# Transistors.net
KiCad netlist of a schematic drawn in EAGLE
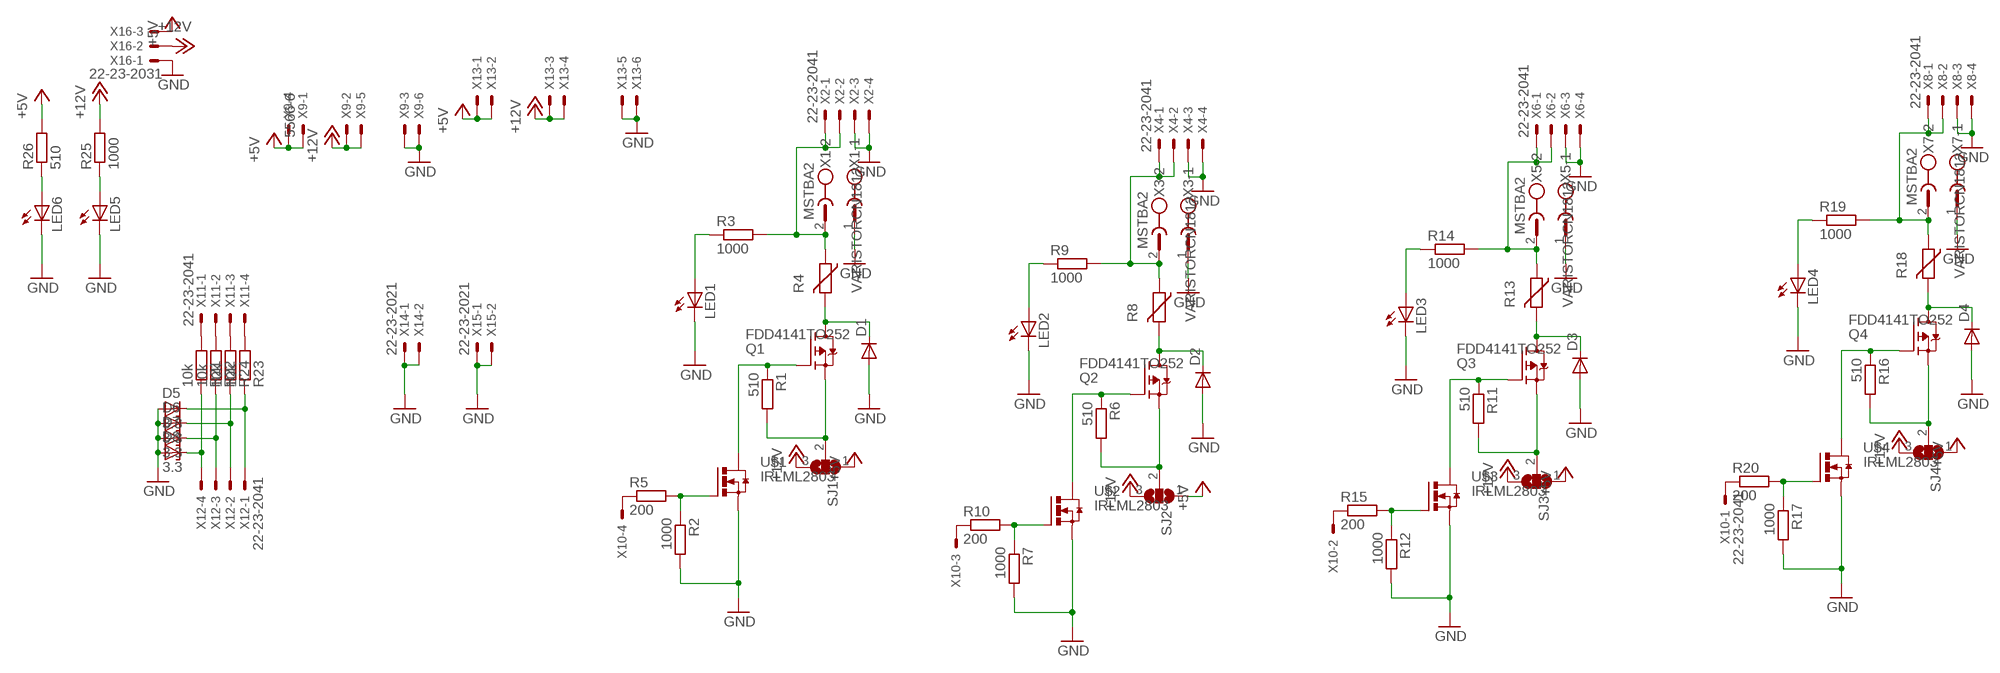
[diagram p0: schematic, sheet 1]

(export (version "E")
  (design (tool "Eeschema 10.0.6"))
  (components
    (comp (ref "D1")
      (value "DIODE-SMB")
      (footprint "eagle-import:SMB")
      (libsource (lib "eagle-import") (part "DIODE-SMB"))
    )
    (comp (ref "D2")
      (value "DIODE-SMB")
      (footprint "eagle-import:SMB")
      (libsource (lib "eagle-import") (part "DIODE-SMB"))
    )
    (comp (ref "D3")
      (value "DIODE-SMB")
      (footprint "eagle-import:SMB")
      (libsource (lib "eagle-import") (part "DIODE-SMB"))
    )
    (comp (ref "D4")
      (value "DIODE-SMB")
      (footprint "eagle-import:SMB")
      (libsource (lib "eagle-import") (part "DIODE-SMB"))
    )
    (comp (ref "D5")
      (value "3.3")
      (footprint "eagle-import:SOD80C")
      (libsource (lib "eagle-import") (part "ZENER-DIODESOD80C"))
    )
    (comp (ref "D6")
      (value "3.3")
      (footprint "eagle-import:SOD80C")
      (libsource (lib "eagle-import") (part "ZENER-DIODESOD80C"))
    )
    (comp (ref "D7")
      (value "3.3")
      (footprint "eagle-import:SOD80C")
      (libsource (lib "eagle-import") (part "ZENER-DIODESOD80C"))
    )
    (comp (ref "D8")
      (value "3.3")
      (footprint "eagle-import:SOD80C")
      (libsource (lib "eagle-import") (part "ZENER-DIODESOD80C"))
    )
    (comp (ref "LED1")
      (value "LEDCHIPLED_1206")
      (footprint "eagle-import:CHIPLED_1206")
      (libsource (lib "eagle-import") (part "LEDCHIPLED_1206"))
    )
    (comp (ref "LED2")
      (value "LEDCHIPLED_1206")
      (footprint "eagle-import:CHIPLED_1206")
      (libsource (lib "eagle-import") (part "LEDCHIPLED_1206"))
    )
    (comp (ref "LED3")
      (value "LEDCHIPLED_1206")
      (footprint "eagle-import:CHIPLED_1206")
      (libsource (lib "eagle-import") (part "LEDCHIPLED_1206"))
    )
    (comp (ref "LED4")
      (value "LEDCHIPLED_1206")
      (footprint "eagle-import:CHIPLED_1206")
      (libsource (lib "eagle-import") (part "LEDCHIPLED_1206"))
    )
    (comp (ref "LED5")
      (value "LEDCHIPLED_1206")
      (footprint "eagle-import:CHIPLED_1206")
      (libsource (lib "eagle-import") (part "LEDCHIPLED_1206"))
    )
    (comp (ref "LED6")
      (value "LEDCHIPLED_1206")
      (footprint "eagle-import:CHIPLED_1206")
      (libsource (lib "eagle-import") (part "LEDCHIPLED_1206"))
    )
    (comp (ref "Q1")
      (value "FDD4141TO252")
      (footprint "eagle-import:TO252")
      (libsource (lib "eagle-import") (part "FDD4141TO252"))
    )
    (comp (ref "Q2")
      (value "FDD4141TO252")
      (footprint "eagle-import:TO252")
      (libsource (lib "eagle-import") (part "FDD4141TO252"))
    )
    (comp (ref "Q3")
      (value "FDD4141TO252")
      (footprint "eagle-import:TO252")
      (libsource (lib "eagle-import") (part "FDD4141TO252"))
    )
    (comp (ref "Q4")
      (value "FDD4141TO252")
      (footprint "eagle-import:TO252")
      (libsource (lib "eagle-import") (part "FDD4141TO252"))
    )
    (comp (ref "R1")
      (value "510")
      (footprint "eagle-import:M0805")
      (libsource (lib "eagle-import") (part "R-EU_M0805"))
    )
    (comp (ref "R2")
      (value "1000")
      (footprint "eagle-import:M0805")
      (libsource (lib "eagle-import") (part "R-EU_M0805"))
    )
    (comp (ref "R3")
      (value "1000")
      (footprint "eagle-import:M0805")
      (libsource (lib "eagle-import") (part "R-EU_M0805"))
    )
    (comp (ref "R4")
      (value "VARISTORCN1812")
      (footprint "eagle-import:CT_CN1812")
      (libsource (lib "eagle-import") (part "VARISTORCN1812"))
    )
    (comp (ref "R5")
      (value "200")
      (footprint "eagle-import:M0805")
      (libsource (lib "eagle-import") (part "R-EU_M0805"))
    )
    (comp (ref "R6")
      (value "510")
      (footprint "eagle-import:M0805")
      (libsource (lib "eagle-import") (part "R-EU_M0805"))
    )
    (comp (ref "R7")
      (value "1000")
      (footprint "eagle-import:M0805")
      (libsource (lib "eagle-import") (part "R-EU_M0805"))
    )
    (comp (ref "R8")
      (value "VARISTORCN1812")
      (footprint "eagle-import:CT_CN1812")
      (libsource (lib "eagle-import") (part "VARISTORCN1812"))
    )
    (comp (ref "R9")
      (value "1000")
      (footprint "eagle-import:M0805")
      (libsource (lib "eagle-import") (part "R-EU_M0805"))
    )
    (comp (ref "R10")
      (value "200")
      (footprint "eagle-import:M0805")
      (libsource (lib "eagle-import") (part "R-EU_M0805"))
    )
    (comp (ref "R11")
      (value "510")
      (footprint "eagle-import:M0805")
      (libsource (lib "eagle-import") (part "R-EU_M0805"))
    )
    (comp (ref "R12")
      (value "1000")
      (footprint "eagle-import:M0805")
      (libsource (lib "eagle-import") (part "R-EU_M0805"))
    )
    (comp (ref "R13")
      (value "VARISTORCN1812")
      (footprint "eagle-import:CT_CN1812")
      (libsource (lib "eagle-import") (part "VARISTORCN1812"))
    )
    (comp (ref "R14")
      (value "1000")
      (footprint "eagle-import:M0805")
      (libsource (lib "eagle-import") (part "R-EU_M0805"))
    )
    (comp (ref "R15")
      (value "200")
      (footprint "eagle-import:M0805")
      (libsource (lib "eagle-import") (part "R-EU_M0805"))
    )
    (comp (ref "R16")
      (value "510")
      (footprint "eagle-import:M0805")
      (libsource (lib "eagle-import") (part "R-EU_M0805"))
    )
    (comp (ref "R17")
      (value "1000")
      (footprint "eagle-import:M0805")
      (libsource (lib "eagle-import") (part "R-EU_M0805"))
    )
    (comp (ref "R18")
      (value "VARISTORCN1812")
      (footprint "eagle-import:CT_CN1812")
      (libsource (lib "eagle-import") (part "VARISTORCN1812"))
    )
    (comp (ref "R19")
      (value "1000")
      (footprint "eagle-import:M0805")
      (libsource (lib "eagle-import") (part "R-EU_M0805"))
    )
    (comp (ref "R20")
      (value "200")
      (footprint "eagle-import:M0805")
      (libsource (lib "eagle-import") (part "R-EU_M0805"))
    )
    (comp (ref "R21")
      (value "10k")
      (footprint "eagle-import:M0805")
      (libsource (lib "eagle-import") (part "R-EU_M0805"))
    )
    (comp (ref "R22")
      (value "10k")
      (footprint "eagle-import:M0805")
      (libsource (lib "eagle-import") (part "R-EU_M0805"))
    )
    (comp (ref "R23")
      (value "10k")
      (footprint "eagle-import:M0805")
      (libsource (lib "eagle-import") (part "R-EU_M0805"))
    )
    (comp (ref "R24")
      (value "10k")
      (footprint "eagle-import:M0805")
      (libsource (lib "eagle-import") (part "R-EU_M0805"))
    )
    (comp (ref "R25")
      (value "1000")
      (footprint "eagle-import:M0805")
      (libsource (lib "eagle-import") (part "R-EU_M0805"))
    )
    (comp (ref "R26")
      (value "510")
      (footprint "eagle-import:M0805")
      (libsource (lib "eagle-import") (part "R-EU_M0805"))
    )
    (comp (ref "SJ1")
      (value "SJ2W")
      (footprint "eagle-import:SJ_2")
      (libsource (lib "eagle-import") (part "SJ2W"))
    )
    (comp (ref "SJ2")
      (value "SJ2W")
      (footprint "eagle-import:SJ_2")
      (libsource (lib "eagle-import") (part "SJ2W"))
    )
    (comp (ref "SJ3")
      (value "SJ2W")
      (footprint "eagle-import:SJ_2")
      (libsource (lib "eagle-import") (part "SJ2W"))
    )
    (comp (ref "SJ4")
      (value "SJ2W")
      (footprint "eagle-import:SJ_2")
      (libsource (lib "eagle-import") (part "SJ2W"))
    )
    (comp (ref "U$1")
      (value "IRLML2803")
      (footprint "eagle-import:SUPER-SOT3")
      (libsource (lib "eagle-import") (part "IRLML2803"))
    )
    (comp (ref "U$2")
      (value "IRLML2803")
      (footprint "eagle-import:SUPER-SOT3")
      (libsource (lib "eagle-import") (part "IRLML2803"))
    )
    (comp (ref "U$3")
      (value "IRLML2803")
      (footprint "eagle-import:SUPER-SOT3")
      (libsource (lib "eagle-import") (part "IRLML2803"))
    )
    (comp (ref "U$4")
      (value "IRLML2803")
      (footprint "eagle-import:SUPER-SOT3")
      (libsource (lib "eagle-import") (part "IRLML2803"))
    )
    (comp (ref "X1")
      (value "MSTBA2")
      (footprint "eagle-import:MSTBA2")
      (fields (field (name "MF") "FARNELL") (field (name "MPN") "1757242"))
      (libsource (lib "eagle-import") (part "MSTBA2"))
    )
    (comp (ref "X2")
      (value "22-23-2041")
      (footprint "eagle-import:22-23-2041")
      (fields (field (name "MF") "MOLEX"))
      (libsource (lib "eagle-import") (part "22-23-2041"))
    )
    (comp (ref "X3")
      (value "MSTBA2")
      (footprint "eagle-import:MSTBA2")
      (fields (field (name "MF") "FARNELL") (field (name "MPN") "1757242"))
      (libsource (lib "eagle-import") (part "MSTBA2"))
    )
    (comp (ref "X4")
      (value "22-23-2041")
      (footprint "eagle-import:22-23-2041")
      (fields (field (name "MF") "MOLEX"))
      (libsource (lib "eagle-import") (part "22-23-2041"))
    )
    (comp (ref "X5")
      (value "MSTBA2")
      (footprint "eagle-import:MSTBA2")
      (fields (field (name "MF") "FARNELL") (field (name "MPN") "1757242"))
      (libsource (lib "eagle-import") (part "MSTBA2"))
    )
    (comp (ref "X6")
      (value "22-23-2041")
      (footprint "eagle-import:22-23-2041")
      (fields (field (name "MF") "MOLEX"))
      (libsource (lib "eagle-import") (part "22-23-2041"))
    )
    (comp (ref "X7")
      (value "MSTBA2")
      (footprint "eagle-import:MSTBA2")
      (fields (field (name "MF") "FARNELL") (field (name "MPN") "1757242"))
      (libsource (lib "eagle-import") (part "MSTBA2"))
    )
    (comp (ref "X8")
      (value "22-23-2041")
      (footprint "eagle-import:22-23-2041")
      (fields (field (name "MF") "MOLEX"))
      (libsource (lib "eagle-import") (part "22-23-2041"))
    )
    (comp (ref "X9")
      (value "5566-6")
      (footprint "eagle-import:5566-6")
      (fields (field (name "MPN") "95566-61002"))
      (libsource (lib "eagle-import") (part "5566-6"))
    )
    (comp (ref "X10")
      (value "22-23-2041")
      (footprint "eagle-import:22-23-2041")
      (fields (field (name "MF") "MOLEX"))
      (libsource (lib "eagle-import") (part "22-23-2041"))
    )
    (comp (ref "X11")
      (value "22-23-2041")
      (footprint "eagle-import:22-23-2041")
      (fields
        (field (name "MF") "MOLEX")
        (field (name "MF_1") "MOLEX")
        (field (name "MPN") "22-23-2041")
        (field (name "OC_FARNELL") "1462920")
        (field (name "OC_NEWARK") "38C0355")
      )
      (libsource (lib "eagle-import") (part "22-23-2041"))
    )
    (comp (ref "X12")
      (value "22-23-2041")
      (footprint "eagle-import:22-23-2041")
      (fields
        (field (name "MF") "MOLEX")
        (field (name "MF_1") "MOLEX")
        (field (name "MPN") "22-23-2041")
        (field (name "OC_FARNELL") "1462920")
        (field (name "OC_NEWARK") "38C0355")
      )
      (libsource (lib "eagle-import") (part "22-23-2041"))
    )
    (comp (ref "X13")
      (value "22-23-2061")
      (footprint "eagle-import:22-23-2061")
      (fields (field (name "MF") "MOLEX"))
      (libsource (lib "eagle-import") (part "22-23-2061"))
    )
    (comp (ref "X14")
      (value "22-23-2021")
      (footprint "eagle-import:22-23-2021")
      (fields (field (name "MF") "MOLEX"))
      (libsource (lib "eagle-import") (part "22-23-2021"))
    )
    (comp (ref "X15")
      (value "22-23-2021")
      (footprint "eagle-import:22-23-2021")
      (fields (field (name "MF") "MOLEX"))
      (libsource (lib "eagle-import") (part "22-23-2021"))
    )
    (comp (ref "X16")
      (value "22-23-2031")
      (footprint "eagle-import:22-23-2031")
      (fields (field (name "MF") "MOLEX"))
      (libsource (lib "eagle-import") (part "22-23-2031"))
    )
  )
  (nets
    (net (code "1") (name "+5V") (class "Default")
      (node (ref "R26") (pin "2") (pinfunction "2_2") (pintype "passive"))
      (node (ref "SJ1") (pin "1") (pinfunction "1_1") (pintype "passive"))
      (node (ref "SJ2") (pin "1") (pinfunction "1_1") (pintype "passive"))
      (node (ref "SJ3") (pin "1") (pinfunction "1_1") (pintype "passive"))
      (node (ref "SJ4") (pin "1") (pinfunction "1_1") (pintype "passive"))
      (node (ref "X13") (pin "1") (pinfunction "S_1") (pintype "passive"))
      (node (ref "X13") (pin "2") (pinfunction "S_2") (pintype "passive"))
      (node (ref "X16") (pin "3") (pinfunction "S_3") (pintype "passive"))
      (node (ref "X9") (pin "1") (pinfunction "S_1") (pintype "passive"))
      (node (ref "X9") (pin "4") (pinfunction "S_4") (pintype "passive"))
    )
    (net (code "2") (name "+12V") (class "Default")
      (node (ref "R25") (pin "2") (pinfunction "2_2") (pintype "passive"))
      (node (ref "SJ1") (pin "3") (pinfunction "3_3") (pintype "passive"))
      (node (ref "SJ2") (pin "3") (pinfunction "3_3") (pintype "passive"))
      (node (ref "SJ3") (pin "3") (pinfunction "3_3") (pintype "passive"))
      (node (ref "SJ4") (pin "3") (pinfunction "3_3") (pintype "passive"))
      (node (ref "X13") (pin "3") (pinfunction "S_3") (pintype "passive"))
      (node (ref "X13") (pin "4") (pinfunction "S_4") (pintype "passive"))
      (node (ref "X16") (pin "2") (pinfunction "S_2") (pintype "passive"))
      (node (ref "X9") (pin "2") (pinfunction "S_2") (pintype "passive"))
      (node (ref "X9") (pin "5") (pinfunction "S_5") (pintype "passive"))
    )
    (net (code "3") (name "GND") (class "Default")
      (node (ref "D1") (pin "A") (pinfunction "A_A") (pintype "passive"))
      (node (ref "D2") (pin "A") (pinfunction "A_A") (pintype "passive"))
      (node (ref "D3") (pin "A") (pinfunction "A_A") (pintype "passive"))
      (node (ref "D4") (pin "A") (pinfunction "A_A") (pintype "passive"))
      (node (ref "D5") (pin "A") (pinfunction "A_A") (pintype "passive"))
      (node (ref "D6") (pin "A") (pinfunction "A_A") (pintype "passive"))
      (node (ref "D7") (pin "A") (pinfunction "A_A") (pintype "passive"))
      (node (ref "D8") (pin "A") (pinfunction "A_A") (pintype "passive"))
      (node (ref "LED1") (pin "C") (pinfunction "C_C") (pintype "passive"))
      (node (ref "LED2") (pin "C") (pinfunction "C_C") (pintype "passive"))
      (node (ref "LED3") (pin "C") (pinfunction "C_C") (pintype "passive"))
      (node (ref "LED4") (pin "C") (pinfunction "C_C") (pintype "passive"))
      (node (ref "LED5") (pin "C") (pinfunction "C_C") (pintype "passive"))
      (node (ref "LED6") (pin "C") (pinfunction "C_C") (pintype "passive"))
      (node (ref "R12") (pin "2") (pinfunction "2_2") (pintype "passive"))
      (node (ref "R17") (pin "2") (pinfunction "2_2") (pintype "passive"))
      (node (ref "R2") (pin "2") (pinfunction "2_2") (pintype "passive"))
      (node (ref "R7") (pin "2") (pinfunction "2_2") (pintype "passive"))
      (node (ref "U$1") (pin "2") (pinfunction "S_2") (pintype "passive"))
      (node (ref "U$2") (pin "2") (pinfunction "S_2") (pintype "passive"))
      (node (ref "U$3") (pin "2") (pinfunction "S_2") (pintype "passive"))
      (node (ref "U$4") (pin "2") (pinfunction "S_2") (pintype "passive"))
      (node (ref "X1") (pin "1") (pinfunction "1_1") (pintype "passive"))
      (node (ref "X13") (pin "5") (pinfunction "S_5") (pintype "passive"))
      (node (ref "X13") (pin "6") (pinfunction "S_6") (pintype "passive"))
      (node (ref "X14") (pin "1") (pinfunction "S_1") (pintype "passive"))
      (node (ref "X14") (pin "2") (pinfunction "S_2") (pintype "passive"))
      (node (ref "X15") (pin "1") (pinfunction "S_1") (pintype "passive"))
      (node (ref "X15") (pin "2") (pinfunction "S_2") (pintype "passive"))
      (node (ref "X16") (pin "1") (pinfunction "S_1") (pintype "passive"))
      (node (ref "X2") (pin "3") (pinfunction "S_3") (pintype "passive"))
      (node (ref "X2") (pin "4") (pinfunction "S_4") (pintype "passive"))
      (node (ref "X3") (pin "1") (pinfunction "1_1") (pintype "passive"))
      (node (ref "X4") (pin "3") (pinfunction "S_3") (pintype "passive"))
      (node (ref "X4") (pin "4") (pinfunction "S_4") (pintype "passive"))
      (node (ref "X5") (pin "1") (pinfunction "1_1") (pintype "passive"))
      (node (ref "X6") (pin "3") (pinfunction "S_3") (pintype "passive"))
      (node (ref "X6") (pin "4") (pinfunction "S_4") (pintype "passive"))
      (node (ref "X7") (pin "1") (pinfunction "1_1") (pintype "passive"))
      (node (ref "X8") (pin "3") (pinfunction "S_3") (pintype "passive"))
      (node (ref "X8") (pin "4") (pinfunction "S_4") (pintype "passive"))
      (node (ref "X9") (pin "3") (pinfunction "S_3") (pintype "passive"))
      (node (ref "X9") (pin "6") (pinfunction "S_6") (pintype "passive"))
    )
    (net (code "4") (name "Net-(LED1-PadA)") (class "Default")
      (node (ref "LED1") (pin "A") (pinfunction "A_A") (pintype "passive"))
      (node (ref "R3") (pin "1") (pinfunction "1_1") (pintype "passive"))
    )
    (net (code "5") (name "Net-(LED2-PadA)") (class "Default")
      (node (ref "LED2") (pin "A") (pinfunction "A_A") (pintype "passive"))
      (node (ref "R9") (pin "1") (pinfunction "1_1") (pintype "passive"))
    )
    (net (code "6") (name "Net-(LED3-PadA)") (class "Default")
      (node (ref "LED3") (pin "A") (pinfunction "A_A") (pintype "passive"))
      (node (ref "R14") (pin "1") (pinfunction "1_1") (pintype "passive"))
    )
    (net (code "7") (name "Net-(LED4-PadA)") (class "Default")
      (node (ref "LED4") (pin "A") (pinfunction "A_A") (pintype "passive"))
      (node (ref "R19") (pin "1") (pinfunction "1_1") (pintype "passive"))
    )
    (net (code "8") (name "Net-(LED5-PadA)") (class "Default")
      (node (ref "LED5") (pin "A") (pinfunction "A_A") (pintype "passive"))
      (node (ref "R25") (pin "1") (pinfunction "1_1") (pintype "passive"))
    )
    (net (code "9") (name "Net-(LED6-PadA)") (class "Default")
      (node (ref "LED6") (pin "A") (pinfunction "A_A") (pintype "passive"))
      (node (ref "R26") (pin "1") (pinfunction "1_1") (pintype "passive"))
    )
    (net (code "10") (name "Net-(Q1-D)") (class "Default")
      (node (ref "D1") (pin "C") (pinfunction "C_C") (pintype "passive"))
      (node (ref "Q1") (pin "3") (pinfunction "D_3") (pintype "passive"))
      (node (ref "R4") (pin "2") (pinfunction "2_2") (pintype "passive"))
    )
    (net (code "11") (name "Net-(Q1-G)") (class "Default")
      (node (ref "Q1") (pin "1") (pinfunction "G_1") (pintype "passive"))
      (node (ref "R1") (pin "1") (pinfunction "1_1") (pintype "passive"))
      (node (ref "U$1") (pin "3") (pinfunction "D_3") (pintype "passive"))
    )
    (net (code "12") (name "Net-(Q1-S)") (class "Default")
      (node (ref "Q1") (pin "2") (pinfunction "S_2") (pintype "passive"))
      (node (ref "R1") (pin "2") (pinfunction "2_2") (pintype "passive"))
      (node (ref "SJ1") (pin "2") (pinfunction "2_2") (pintype "passive"))
    )
    (net (code "13") (name "Net-(Q2-D)") (class "Default")
      (node (ref "D2") (pin "C") (pinfunction "C_C") (pintype "passive"))
      (node (ref "Q2") (pin "3") (pinfunction "D_3") (pintype "passive"))
      (node (ref "R8") (pin "2") (pinfunction "2_2") (pintype "passive"))
    )
    (net (code "14") (name "Net-(Q2-G)") (class "Default")
      (node (ref "Q2") (pin "1") (pinfunction "G_1") (pintype "passive"))
      (node (ref "R6") (pin "1") (pinfunction "1_1") (pintype "passive"))
      (node (ref "U$2") (pin "3") (pinfunction "D_3") (pintype "passive"))
    )
    (net (code "15") (name "Net-(Q2-S)") (class "Default")
      (node (ref "Q2") (pin "2") (pinfunction "S_2") (pintype "passive"))
      (node (ref "R6") (pin "2") (pinfunction "2_2") (pintype "passive"))
      (node (ref "SJ2") (pin "2") (pinfunction "2_2") (pintype "passive"))
    )
    (net (code "16") (name "Net-(Q3-D)") (class "Default")
      (node (ref "D3") (pin "C") (pinfunction "C_C") (pintype "passive"))
      (node (ref "Q3") (pin "3") (pinfunction "D_3") (pintype "passive"))
      (node (ref "R13") (pin "2") (pinfunction "2_2") (pintype "passive"))
    )
    (net (code "17") (name "Net-(Q3-G)") (class "Default")
      (node (ref "Q3") (pin "1") (pinfunction "G_1") (pintype "passive"))
      (node (ref "R11") (pin "1") (pinfunction "1_1") (pintype "passive"))
      (node (ref "U$3") (pin "3") (pinfunction "D_3") (pintype "passive"))
    )
    (net (code "18") (name "Net-(Q3-S)") (class "Default")
      (node (ref "Q3") (pin "2") (pinfunction "S_2") (pintype "passive"))
      (node (ref "R11") (pin "2") (pinfunction "2_2") (pintype "passive"))
      (node (ref "SJ3") (pin "2") (pinfunction "2_2") (pintype "passive"))
    )
    (net (code "19") (name "Net-(Q4-D)") (class "Default")
      (node (ref "D4") (pin "C") (pinfunction "C_C") (pintype "passive"))
      (node (ref "Q4") (pin "3") (pinfunction "D_3") (pintype "passive"))
      (node (ref "R18") (pin "2") (pinfunction "2_2") (pintype "passive"))
    )
    (net (code "20") (name "Net-(Q4-G)") (class "Default")
      (node (ref "Q4") (pin "1") (pinfunction "G_1") (pintype "passive"))
      (node (ref "R16") (pin "1") (pinfunction "1_1") (pintype "passive"))
      (node (ref "U$4") (pin "3") (pinfunction "D_3") (pintype "passive"))
    )
    (net (code "21") (name "Net-(Q4-S)") (class "Default")
      (node (ref "Q4") (pin "2") (pinfunction "S_2") (pintype "passive"))
      (node (ref "R16") (pin "2") (pinfunction "2_2") (pintype "passive"))
      (node (ref "SJ4") (pin "2") (pinfunction "2_2") (pintype "passive"))
    )
    (net (code "22") (name "Net-(U$1-G)") (class "Default")
      (node (ref "R2") (pin "1") (pinfunction "1_1") (pintype "passive"))
      (node (ref "R5") (pin "2") (pinfunction "2_2") (pintype "passive"))
      (node (ref "U$1") (pin "1") (pinfunction "G_1") (pintype "passive"))
    )
    (net (code "23") (name "Net-(U$2-G)") (class "Default")
      (node (ref "R10") (pin "2") (pinfunction "2_2") (pintype "passive"))
      (node (ref "R7") (pin "1") (pinfunction "1_1") (pintype "passive"))
      (node (ref "U$2") (pin "1") (pinfunction "G_1") (pintype "passive"))
    )
    (net (code "24") (name "Net-(U$3-G)") (class "Default")
      (node (ref "R12") (pin "1") (pinfunction "1_1") (pintype "passive"))
      (node (ref "R15") (pin "2") (pinfunction "2_2") (pintype "passive"))
      (node (ref "U$3") (pin "1") (pinfunction "G_1") (pintype "passive"))
    )
    (net (code "25") (name "Net-(U$4-G)") (class "Default")
      (node (ref "R17") (pin "1") (pinfunction "1_1") (pintype "passive"))
      (node (ref "R20") (pin "2") (pinfunction "2_2") (pintype "passive"))
      (node (ref "U$4") (pin "1") (pinfunction "G_1") (pintype "passive"))
    )
    (net (code "26") (name "Net-(X1B-1)") (class "Default")
      (node (ref "R3") (pin "2") (pinfunction "2_2") (pintype "passive"))
      (node (ref "R4") (pin "1") (pinfunction "1_1") (pintype "passive"))
      (node (ref "X1") (pin "2") (pinfunction "1_2") (pintype "passive"))
      (node (ref "X2") (pin "1") (pinfunction "S_1") (pintype "passive"))
      (node (ref "X2") (pin "2") (pinfunction "S_2") (pintype "passive"))
    )
    (net (code "27") (name "Net-(X3B-1)") (class "Default")
      (node (ref "R8") (pin "1") (pinfunction "1_1") (pintype "passive"))
      (node (ref "R9") (pin "2") (pinfunction "2_2") (pintype "passive"))
      (node (ref "X3") (pin "2") (pinfunction "1_2") (pintype "passive"))
      (node (ref "X4") (pin "1") (pinfunction "S_1") (pintype "passive"))
      (node (ref "X4") (pin "2") (pinfunction "S_2") (pintype "passive"))
    )
    (net (code "28") (name "Net-(X5B-1)") (class "Default")
      (node (ref "R13") (pin "1") (pinfunction "1_1") (pintype "passive"))
      (node (ref "R14") (pin "2") (pinfunction "2_2") (pintype "passive"))
      (node (ref "X5") (pin "2") (pinfunction "1_2") (pintype "passive"))
      (node (ref "X6") (pin "1") (pinfunction "S_1") (pintype "passive"))
      (node (ref "X6") (pin "2") (pinfunction "S_2") (pintype "passive"))
    )
    (net (code "29") (name "Net-(X7B-1)") (class "Default")
      (node (ref "R18") (pin "1") (pinfunction "1_1") (pintype "passive"))
      (node (ref "R19") (pin "2") (pinfunction "2_2") (pintype "passive"))
      (node (ref "X7") (pin "2") (pinfunction "1_2") (pintype "passive"))
      (node (ref "X8") (pin "1") (pinfunction "S_1") (pintype "passive"))
      (node (ref "X8") (pin "2") (pinfunction "S_2") (pintype "passive"))
    )
    (net (code "30") (name "Net-(X10A-S)") (class "Default")
      (node (ref "R20") (pin "1") (pinfunction "1_1") (pintype "passive"))
      (node (ref "X10") (pin "1") (pinfunction "S_1") (pintype "passive"))
    )
    (net (code "31") (name "Net-(X10B-S)") (class "Default")
      (node (ref "R15") (pin "1") (pinfunction "1_1") (pintype "passive"))
      (node (ref "X10") (pin "2") (pinfunction "S_2") (pintype "passive"))
    )
    (net (code "32") (name "Net-(X10C-S)") (class "Default")
      (node (ref "R10") (pin "1") (pinfunction "1_1") (pintype "passive"))
      (node (ref "X10") (pin "3") (pinfunction "S_3") (pintype "passive"))
    )
    (net (code "33") (name "Net-(X10D-S)") (class "Default")
      (node (ref "R5") (pin "1") (pinfunction "1_1") (pintype "passive"))
      (node (ref "X10") (pin "4") (pinfunction "S_4") (pintype "passive"))
    )
    (net (code "34") (name "Net-(X11A-S)") (class "Default")
      (node (ref "R21") (pin "2") (pinfunction "2_2") (pintype "passive"))
      (node (ref "X11") (pin "1") (pinfunction "S_1") (pintype "passive"))
    )
    (net (code "35") (name "Net-(X11B-S)") (class "Default")
      (node (ref "R22") (pin "2") (pinfunction "2_2") (pintype "passive"))
      (node (ref "X11") (pin "2") (pinfunction "S_2") (pintype "passive"))
    )
    (net (code "36") (name "Net-(X11C-S)") (class "Default")
      (node (ref "R24") (pin "2") (pinfunction "2_2") (pintype "passive"))
      (node (ref "X11") (pin "3") (pinfunction "S_3") (pintype "passive"))
    )
    (net (code "37") (name "Net-(X11D-S)") (class "Default")
      (node (ref "R23") (pin "2") (pinfunction "2_2") (pintype "passive"))
      (node (ref "X11") (pin "4") (pinfunction "S_4") (pintype "passive"))
    )
    (net (code "38") (name "Net-(X12A-S)") (class "Default")
      (node (ref "D5") (pin "C") (pinfunction "C_C") (pintype "passive"))
      (node (ref "R23") (pin "1") (pinfunction "1_1") (pintype "passive"))
      (node (ref "X12") (pin "1") (pinfunction "S_1") (pintype "passive"))
    )
    (net (code "39") (name "Net-(X12B-S)") (class "Default")
      (node (ref "D6") (pin "C") (pinfunction "C_C") (pintype "passive"))
      (node (ref "R24") (pin "1") (pinfunction "1_1") (pintype "passive"))
      (node (ref "X12") (pin "2") (pinfunction "S_2") (pintype "passive"))
    )
    (net (code "40") (name "Net-(X12C-S)") (class "Default")
      (node (ref "D7") (pin "C") (pinfunction "C_C") (pintype "passive"))
      (node (ref "R22") (pin "1") (pinfunction "1_1") (pintype "passive"))
      (node (ref "X12") (pin "3") (pinfunction "S_3") (pintype "passive"))
    )
    (net (code "41") (name "Net-(X12D-S)") (class "Default")
      (node (ref "D8") (pin "C") (pinfunction "C_C") (pintype "passive"))
      (node (ref "R21") (pin "1") (pinfunction "1_1") (pintype "passive"))
      (node (ref "X12") (pin "4") (pinfunction "S_4") (pintype "passive"))
    )
  )
)
